# controller_rev3_1.net
KiCad netlist of a schematic drawn in EAGLE
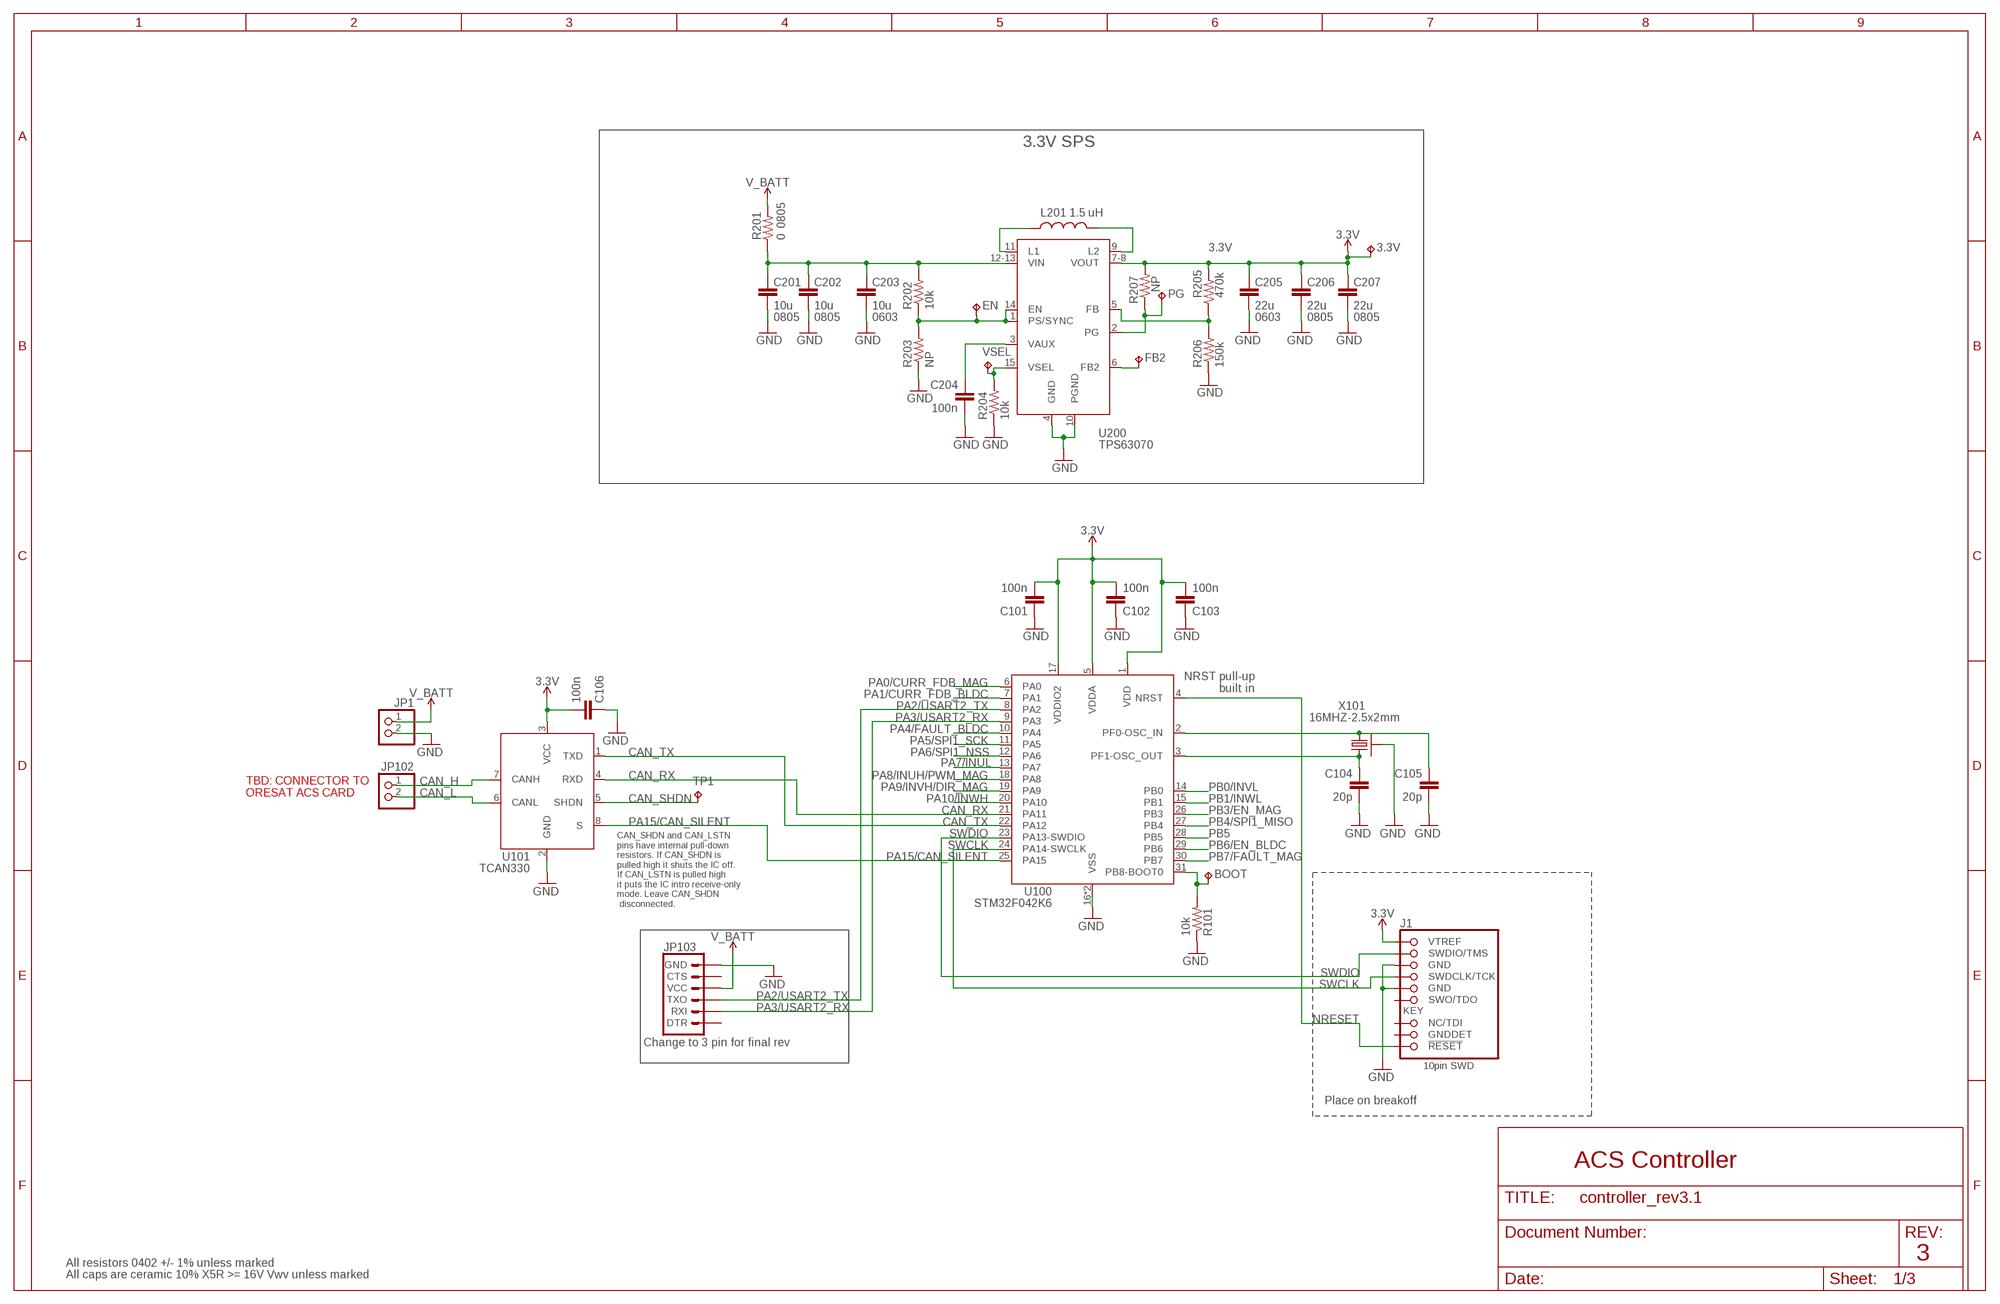
[diagram p0: schematic, sheet 1]
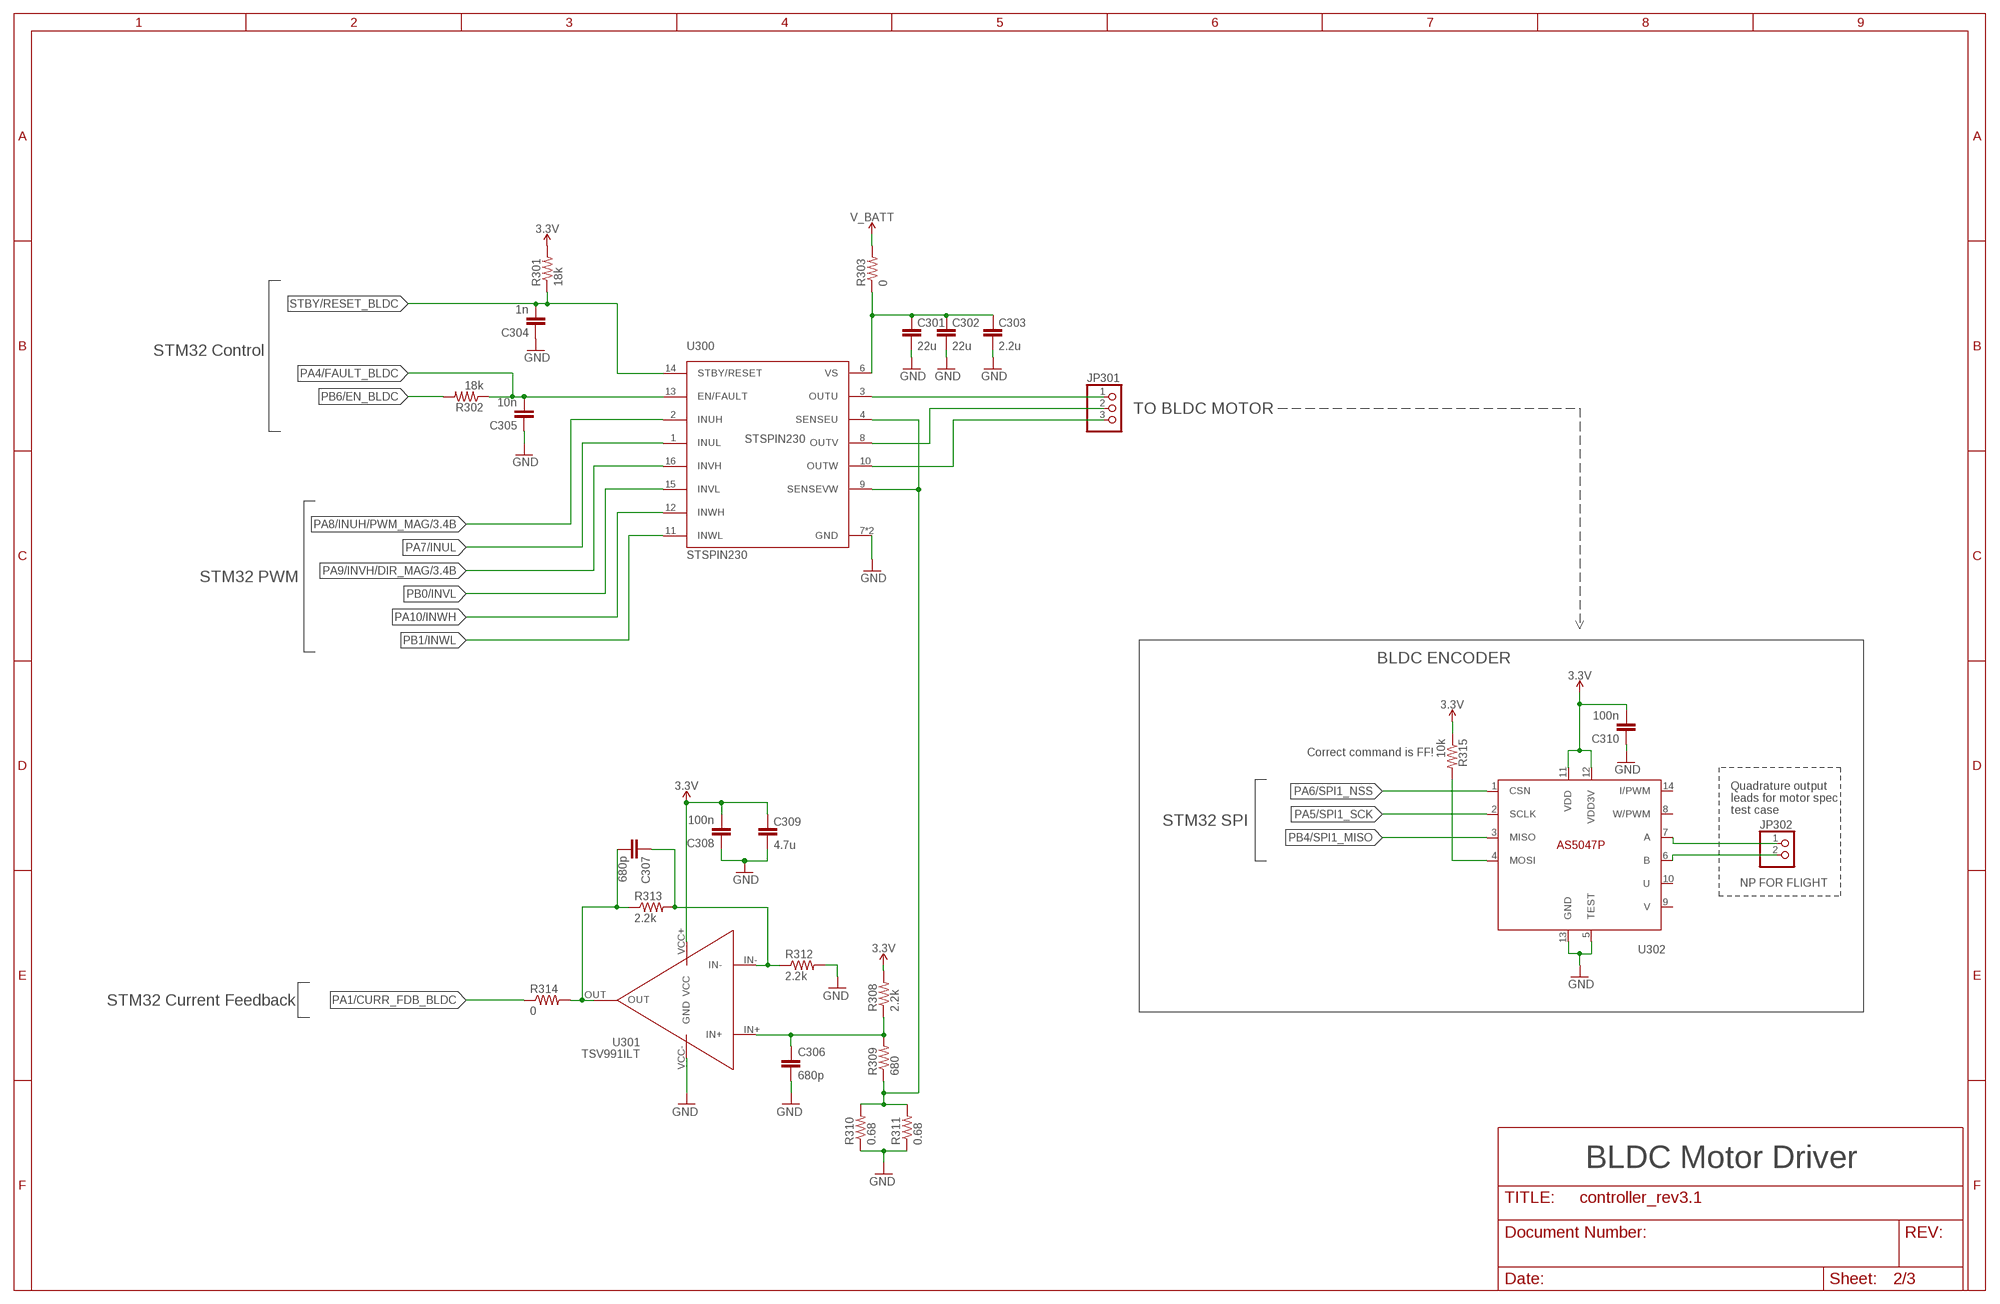
[diagram p1: schematic, sheet 2]
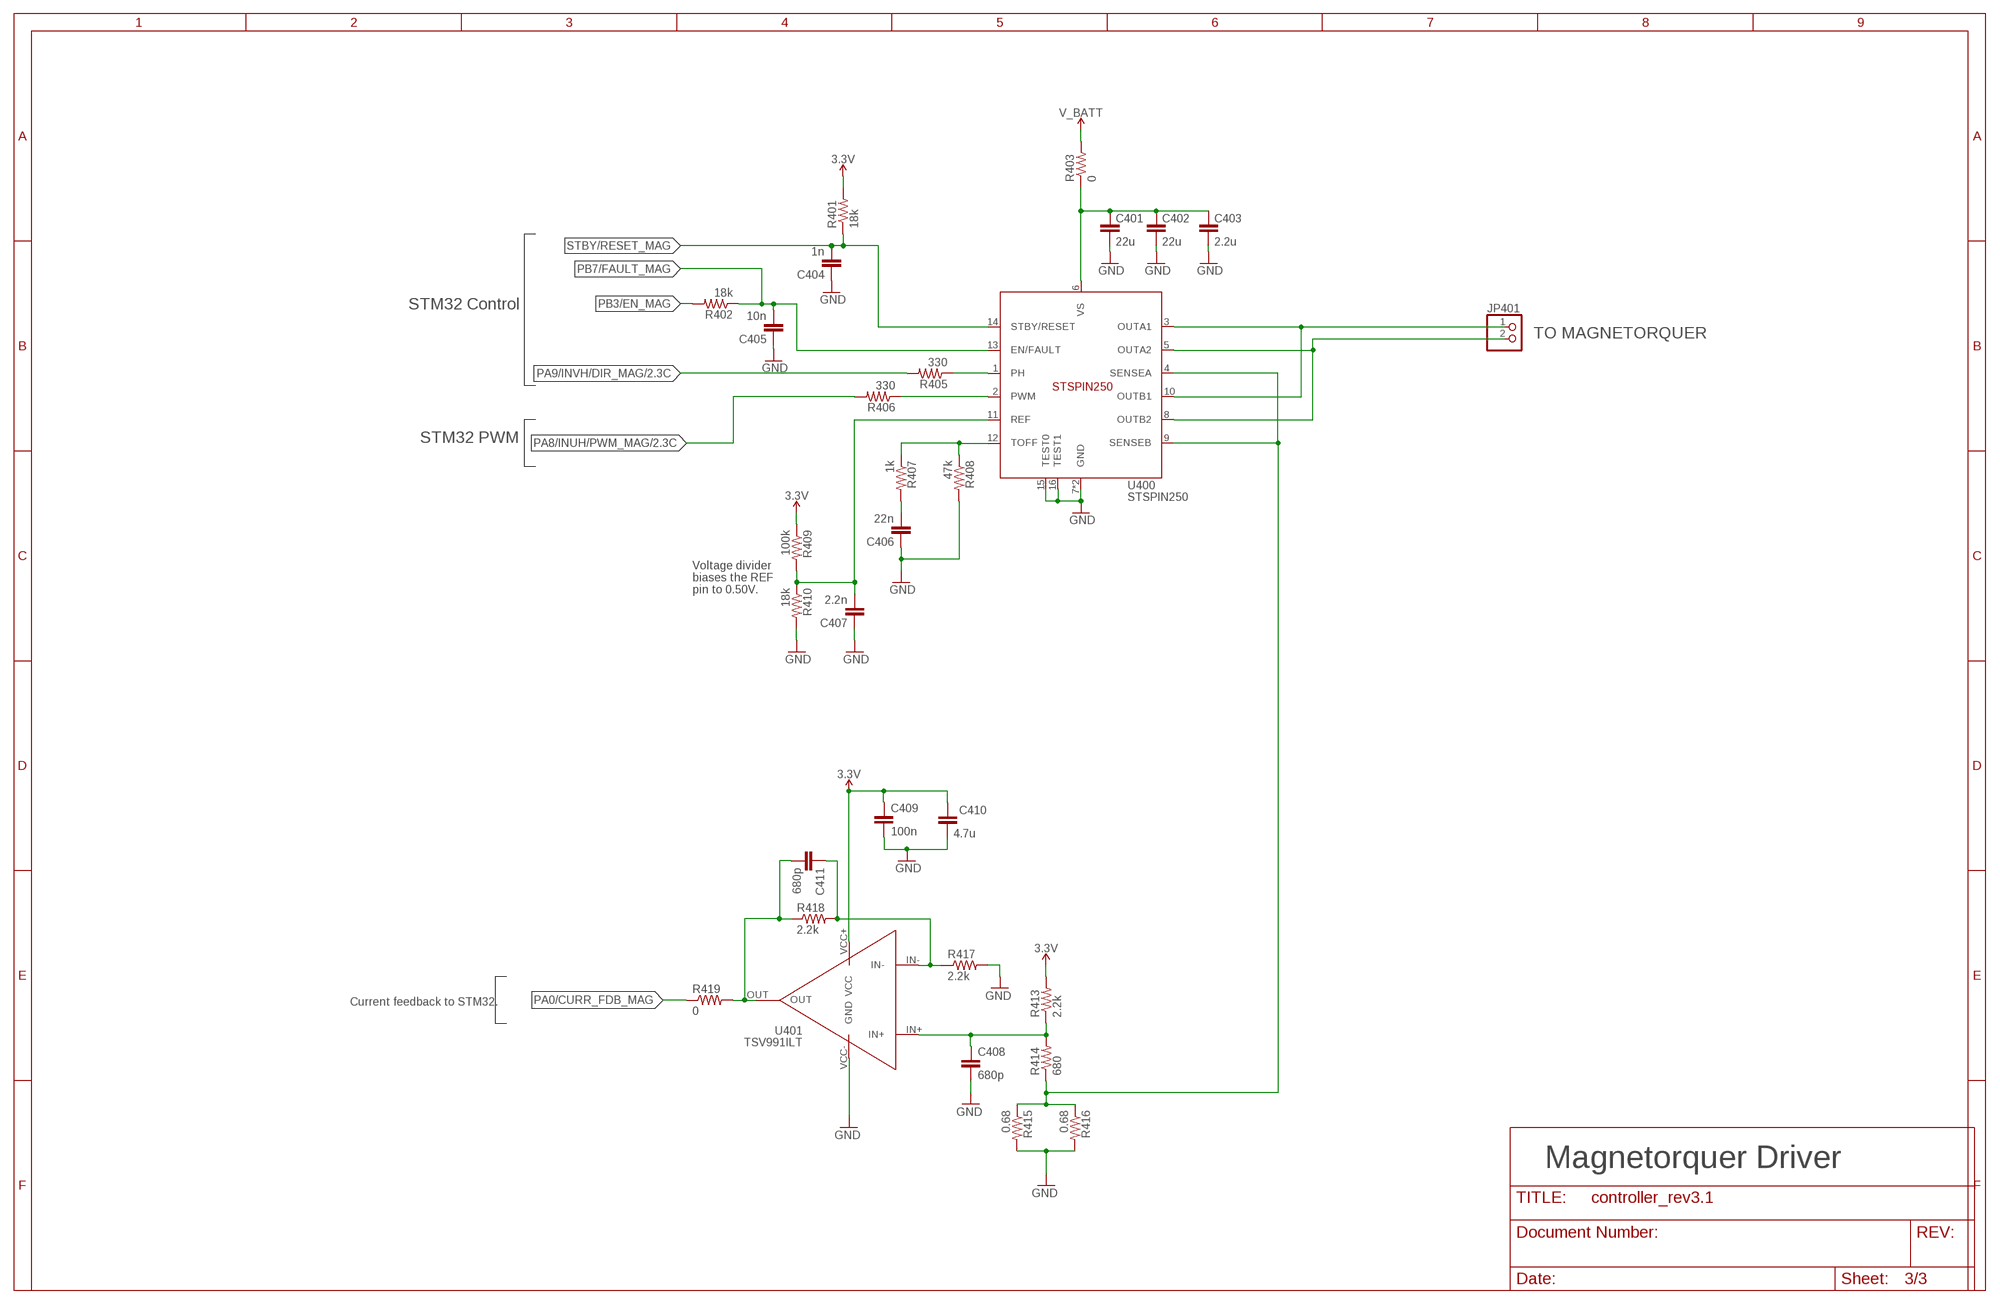
[diagram p2: schematic, sheet 3]

(export (version "E")
  (design (tool "Eeschema 10.0.6"))
  (components
    (comp (ref "3.3V")
      (value "TPTP15SQ")
      (footprint "eagle-import:TP15SQ")
      (libsource (lib "eagle-import") (part "TPTP15SQ"))
    )
    (comp (ref "BOOT")
      (value "TPTP15SQ")
      (footprint "eagle-import:TP15SQ")
      (libsource (lib "eagle-import") (part "TPTP15SQ"))
    )
    (comp (ref "C101")
      (value "100n")
      (footprint "eagle-import:.0402-B-NOSILK")
      (fields (field (name "MFR") "Samsung") (field (name "MPN") "CL05B104KO5NNNC"))
      (libsource (lib "eagle-import") (part "rcl_custom_C-EU0402-B-NOSILK"))
    )
    (comp (ref "C102")
      (value "100n")
      (footprint "eagle-import:.0402-B-NOSILK")
      (fields (field (name "MFR") "Samsung") (field (name "MPN") "CL05B104KO5NNNC"))
      (libsource (lib "eagle-import") (part "rcl_custom_C-EU0402-B-NOSILK"))
    )
    (comp (ref "C103")
      (value "100n")
      (footprint "eagle-import:.0402-B-NOSILK")
      (fields (field (name "MFR") "Samsung") (field (name "MPN") "CL05B104KO5NNNC"))
      (libsource (lib "eagle-import") (part "rcl_custom_C-EU0402-B-NOSILK"))
    )
    (comp (ref "C104")
      (value "20p")
      (footprint "eagle-import:.0402-B-NOSILK")
      (fields (field (name "MFR") "Samsung") (field (name "MPN") "CL05C200JB51PNC"))
      (libsource (lib "eagle-import") (part "rcl_custom_C-EU0402-B-NOSILK"))
    )
    (comp (ref "C105")
      (value "20p")
      (footprint "eagle-import:.0402-B-NOSILK")
      (fields (field (name "MFR") "Samsung") (field (name "MPN") "CL05C200JB51PNC"))
      (libsource (lib "eagle-import") (part "rcl_custom_C-EU0402-B-NOSILK"))
    )
    (comp (ref "C106")
      (value "100n")
      (footprint "eagle-import:.0402-B-NOSILK")
      (fields (field (name "MFR") "Samsung") (field (name "MPN") "CL05B104KO5NNNC"))
      (libsource (lib "eagle-import") (part "rcl_custom_C-EU0402-B-NOSILK"))
    )
    (comp (ref "C201")
      (value "10u")
      (footprint "eagle-import:.0805-B-NOSILK")
      (libsource (lib "eagle-import") (part "C-EU0805-B-NOSILK"))
    )
    (comp (ref "C202")
      (value "10u")
      (footprint "eagle-import:.0805-B-NOSILK")
      (libsource (lib "eagle-import") (part "C-EU0805-B-NOSILK"))
    )
    (comp (ref "C203")
      (value "10u")
      (footprint "eagle-import:.0603-B-NOSILK")
      (fields (field (name "MFR") "Samsung") (field (name "MPN") "CL05B104KO5NNNC"))
      (libsource (lib "eagle-import") (part "C-EU0603-B-NOSILK"))
    )
    (comp (ref "C204")
      (value "100n")
      (footprint "eagle-import:.0402-B-NOSILK")
      (fields (field (name "MFR") "Samsung") (field (name "MPN") "CL05B104KO5NNNC"))
      (libsource (lib "eagle-import") (part "rcl_custom_C-EU0402-B-NOSILK"))
    )
    (comp (ref "C205")
      (value "22u")
      (footprint "eagle-import:.0603-B-NOSILK")
      (fields (field (name "MFR") "Samsung") (field (name "MPN") "CL05B104KO5NNNC"))
      (libsource (lib "eagle-import") (part "C-EU0603-B-NOSILK"))
    )
    (comp (ref "C206")
      (value "22u")
      (footprint "eagle-import:.0805-B-NOSILK")
      (libsource (lib "eagle-import") (part "C-EU0805-B-NOSILK"))
    )
    (comp (ref "C207")
      (value "22u")
      (footprint "eagle-import:.0805-B-NOSILK")
      (libsource (lib "eagle-import") (part "C-EU0805-B-NOSILK"))
    )
    (comp (ref "EN")
      (value "TPTP15SQ")
      (footprint "eagle-import:TP15SQ")
      (libsource (lib "eagle-import") (part "TPTP15SQ"))
    )
    (comp (ref "FB2")
      (value "TPTP15SQ")
      (footprint "eagle-import:TP15SQ")
      (libsource (lib "eagle-import") (part "TPTP15SQ"))
    )
    (comp (ref "J1")
      (value "1.27MM-SWD-CONNECTOR")
      (footprint "eagle-import:1.27MM_2X5")
      (libsource (lib "eagle-import") (part "1.27MM-SWD-CONNECTOR"))
    )
    (comp (ref "JP1")
      (value "PINHD-1X2")
      (footprint "eagle-import:1X02")
      (libsource (lib "eagle-import") (part "PINHD-1X2"))
    )
    (comp (ref "JP102")
      (value "PINHD-1X2")
      (footprint "eagle-import:1X02")
      (libsource (lib "eagle-import") (part "PINHD-1X2"))
    )
    (comp (ref "JP103")
      (value "6_PIN_SERIAL_TARGETSILK")
      (footprint "eagle-import:6_PIN_SERIAL_TARGET_SIDE_W_SILK")
      (libsource (lib "eagle-import") (part "6_PIN_SERIAL_TARGETSILK"))
    )
    (comp (ref "L201")
      (value "1.5 uH")
      (footprint "eagle-import:L-COILCRAFT-XFL4020")
      (fields (field (name "MFR") "Coilcraft") (field (name "MPN") "XFL4020-152ME"))
      (libsource (lib "eagle-import") (part "L-COILCRAFT-XFL4020"))
    )
    (comp (ref "PG")
      (value "TPTP15SQ")
      (footprint "eagle-import:TP15SQ")
      (libsource (lib "eagle-import") (part "TPTP15SQ"))
    )
    (comp (ref "R101")
      (value "10k")
      (footprint "eagle-import:.0402-B-NOSILK")
      (fields (field (name "MFR") "Samsung") (field (name "MPN") "RC1005F6653CS"))
      (libsource (lib "eagle-import") (part "rcl_custom_R-US_0402-B-NOSILK"))
    )
    (comp (ref "R201")
      (value "0")
      (footprint "eagle-import:.0805-B-NOSILK")
      (fields (field (name "MFR") "Rohm") (field (name "MPN") "MCR10EZPJ000"))
      (libsource (lib "eagle-import") (part "rcl_custom_R-US_0805-B-NOSILK"))
    )
    (comp (ref "R202")
      (value "10k")
      (footprint "eagle-import:.0402-B-NOSILK")
      (fields (field (name "MFR") "Samsung") (field (name "MPN") "RC1005F6653CS"))
      (libsource (lib "eagle-import") (part "rcl_custom_R-US_0402-B-NOSILK"))
    )
    (comp (ref "R203")
      (value "NP")
      (footprint "eagle-import:.0402-B-NOSILK")
      (fields (field (name "MFR") "Samsung") (field (name "MPN") "RC1005F6653CS"))
      (libsource (lib "eagle-import") (part "rcl_custom_R-US_0402-B-NOSILK"))
    )
    (comp (ref "R204")
      (value "10k")
      (footprint "eagle-import:.0402-B-NOSILK")
      (fields (field (name "MFR") "Samsung") (field (name "MPN") "RC1005F6653CS"))
      (libsource (lib "eagle-import") (part "rcl_custom_R-US_0402-B-NOSILK"))
    )
    (comp (ref "R205")
      (value "470k")
      (footprint "eagle-import:.0402-B-NOSILK")
      (fields (field (name "MFR") "Samsung") (field (name "MPN") "RC1005F6653CS"))
      (libsource (lib "eagle-import") (part "rcl_custom_R-US_0402-B-NOSILK"))
    )
    (comp (ref "R206")
      (value "150k")
      (footprint "eagle-import:.0402-B-NOSILK")
      (fields (field (name "MFR") "Samsung") (field (name "MPN") "RC1005F6653CS"))
      (libsource (lib "eagle-import") (part "rcl_custom_R-US_0402-B-NOSILK"))
    )
    (comp (ref "R207")
      (value "NP")
      (footprint "eagle-import:.0402-B-NOSILK")
      (fields (field (name "MFR") "Samsung") (field (name "MPN") "RC1005F6653CS"))
      (libsource (lib "eagle-import") (part "rcl_custom_R-US_0402-B-NOSILK"))
    )
    (comp (ref "TP1")
      (value "TPTP06R")
      (footprint "eagle-import:TP06R")
      (libsource (lib "eagle-import") (part "TPTP06R"))
    )
    (comp (ref "U100")
      (value "STM32F042K6")
      (footprint "eagle-import:QFP32-7X7")
      (fields (field (name "MFR") "STMicroelectronics") (field (name "MPN") "STM32F042K6T7"))
      (libsource (lib "eagle-import") (part "STM32F042K6"))
    )
    (comp (ref "U101")
      (value "TCAN330")
      (footprint "eagle-import:SOT23-8_TI-DCN")
      (fields (field (name "MFR") "Texas Instruments") (field (name "MPN") "TCAN330GDCNT"))
      (libsource (lib "eagle-import") (part "TCAN330"))
    )
    (comp (ref "U200")
      (value "TPS63070")
      (footprint "eagle-import:TPS63070X")
      (libsource (lib "eagle-import") (part "TPS63070X"))
    )
    (comp (ref "VSEL")
      (value "TPTP15SQ")
      (footprint "eagle-import:TP15SQ")
      (libsource (lib "eagle-import") (part "TPTP15SQ"))
    )
    (comp (ref "X101")
      (value "16MHZ-2.5x2mm")
      (footprint "eagle-import:CRYSTAL_2.5X2")
      (fields (field (name "MFR") "ECS Inc.") (field (name "MPN") "ECS-160-10-36Q-ES-TR"))
      (libsource (lib "eagle-import") (part "CRYSTAL-WITH-GND"))
    )
    (comp (ref "C401")
      (value "22u")
      (footprint "eagle-import:.0603-B-NOSILK")
      (fields (field (name "MFR") "Samsung") (field (name "MPN") "CL05B104KO5NNNC"))
      (libsource (lib "eagle-import") (part "C-EU0603-B-NOSILK"))
    )
    (comp (ref "C402")
      (value "22u")
      (footprint "eagle-import:.0603-B-NOSILK")
      (fields (field (name "MFR") "Samsung") (field (name "MPN") "CL05B104KO5NNNC"))
      (libsource (lib "eagle-import") (part "C-EU0603-B-NOSILK"))
    )
    (comp (ref "C403")
      (value "2.2u")
      (footprint "eagle-import:.0603-B-NOSILK")
      (fields (field (name "MFR") "Samsung") (field (name "MPN") "CL05B104KO5NNNC"))
      (libsource (lib "eagle-import") (part "C-EU0603-B-NOSILK"))
    )
    (comp (ref "C404")
      (value "1n")
      (footprint "eagle-import:.0402-B-NOSILK")
      (fields (field (name "MFR") "Samsung") (field (name "MPN") "CL05B104KO5NNNC"))
      (libsource (lib "eagle-import") (part "rcl_custom_C-EU0402-B-NOSILK"))
    )
    (comp (ref "C405")
      (value "10n")
      (footprint "eagle-import:.0402-B-NOSILK")
      (fields (field (name "MFR") "Samsung") (field (name "MPN") "CL05B104KO5NNNC"))
      (libsource (lib "eagle-import") (part "rcl_custom_C-EU0402-B-NOSILK"))
    )
    (comp (ref "C406")
      (value "22n")
      (footprint "eagle-import:.0402-B-NOSILK")
      (fields (field (name "MFR") "Samsung") (field (name "MPN") "CL05B104KO5NNNC"))
      (libsource (lib "eagle-import") (part "rcl_custom_C-EU0402-B-NOSILK"))
    )
    (comp (ref "C407")
      (value "2.2n")
      (footprint "eagle-import:.0402-B-NOSILK")
      (fields (field (name "MFR") "Samsung") (field (name "MPN") "CL05B104KO5NNNC"))
      (libsource (lib "eagle-import") (part "rcl_custom_C-EU0402-B-NOSILK"))
    )
    (comp (ref "C408")
      (value "680p")
      (footprint "eagle-import:.0402-B-NOSILK")
      (fields (field (name "MFR") "Samsung") (field (name "MPN") "CL05B104KO5NNNC"))
      (libsource (lib "eagle-import") (part "rcl_custom_C-EU0402-B-NOSILK"))
    )
    (comp (ref "C409")
      (value "100n")
      (footprint "eagle-import:.0402-B-NOSILK")
      (fields (field (name "MFR") "Samsung") (field (name "MPN") "CL05B104KO5NNNC"))
      (libsource (lib "eagle-import") (part "rcl_custom_C-EU0402-B-NOSILK"))
    )
    (comp (ref "C410")
      (value "4.7u")
      (footprint "eagle-import:.0603-B-NOSILK")
      (fields (field (name "MFR") "Samsung") (field (name "MPN") "CL05B104KO5NNNC"))
      (libsource (lib "eagle-import") (part "C-EU0603-B-NOSILK"))
    )
    (comp (ref "C411")
      (value "680p")
      (footprint "eagle-import:.0402-B-NOSILK")
      (fields (field (name "MFR") "Samsung") (field (name "MPN") "CL05B104KO5NNNC"))
      (libsource (lib "eagle-import") (part "rcl_custom_C-EU0402-B-NOSILK"))
    )
    (comp (ref "JP401")
      (value "PINHD-1X2")
      (footprint "eagle-import:1X02")
      (libsource (lib "eagle-import") (part "PINHD-1X2"))
    )
    (comp (ref "R401")
      (value "18k")
      (footprint "eagle-import:.0402-B-NOSILK")
      (fields (field (name "MFR") "Samsung") (field (name "MPN") "RC1005F6653CS"))
      (libsource (lib "eagle-import") (part "rcl_custom_R-US_0402-B-NOSILK"))
    )
    (comp (ref "R402")
      (value "18k")
      (footprint "eagle-import:.0402-B-NOSILK")
      (fields (field (name "MFR") "Samsung") (field (name "MPN") "RC1005F6653CS"))
      (libsource (lib "eagle-import") (part "rcl_custom_R-US_0402-B-NOSILK"))
    )
    (comp (ref "R403")
      (value "0")
      (footprint "eagle-import:.0805-B-NOSILK")
      (libsource (lib "eagle-import") (part "R-US_0805-B-NOSILK"))
    )
    (comp (ref "R405")
      (value "330")
      (footprint "eagle-import:.0402-B-NOSILK")
      (fields (field (name "MFR") "Samsung") (field (name "MPN") "RC1005F6653CS"))
      (libsource (lib "eagle-import") (part "rcl_custom_R-US_0402-B-NOSILK"))
    )
    (comp (ref "R406")
      (value "330")
      (footprint "eagle-import:.0402-B-NOSILK")
      (fields (field (name "MFR") "Samsung") (field (name "MPN") "RC1005F6653CS"))
      (libsource (lib "eagle-import") (part "rcl_custom_R-US_0402-B-NOSILK"))
    )
    (comp (ref "R407")
      (value "1k")
      (footprint "eagle-import:.0402-B-NOSILK")
      (fields (field (name "MFR") "Samsung") (field (name "MPN") "RC1005F6653CS"))
      (libsource (lib "eagle-import") (part "rcl_custom_R-US_0402-B-NOSILK"))
    )
    (comp (ref "R408")
      (value "47k")
      (footprint "eagle-import:.0402-B-NOSILK")
      (fields (field (name "MFR") "Samsung") (field (name "MPN") "RC1005F6653CS"))
      (libsource (lib "eagle-import") (part "rcl_custom_R-US_0402-B-NOSILK"))
    )
    (comp (ref "R409")
      (value "100k")
      (footprint "eagle-import:.0402-B-NOSILK")
      (fields (field (name "MFR") "Samsung") (field (name "MPN") "RC1005F6653CS"))
      (libsource (lib "eagle-import") (part "rcl_custom_R-US_0402-B-NOSILK"))
    )
    (comp (ref "R410")
      (value "18k")
      (footprint "eagle-import:.0402-B-NOSILK")
      (fields (field (name "MFR") "Samsung") (field (name "MPN") "RC1005F6653CS"))
      (libsource (lib "eagle-import") (part "rcl_custom_R-US_0402-B-NOSILK"))
    )
    (comp (ref "R413")
      (value "2.2k")
      (footprint "eagle-import:.0402-B-NOSILK")
      (fields (field (name "MFR") "Samsung") (field (name "MPN") "RC1005F6653CS"))
      (libsource (lib "eagle-import") (part "rcl_custom_R-US_0402-B-NOSILK"))
    )
    (comp (ref "R414")
      (value "680")
      (footprint "eagle-import:.0402-B-NOSILK")
      (fields (field (name "MFR") "Samsung") (field (name "MPN") "RC1005F6653CS"))
      (libsource (lib "eagle-import") (part "rcl_custom_R-US_0402-B-NOSILK"))
    )
    (comp (ref "R415")
      (value "0.68")
      (footprint "eagle-import:.0805-B-NOSILK")
      (libsource (lib "eagle-import") (part "R-US_0805-B-NOSILK"))
    )
    (comp (ref "R416")
      (value "0.68")
      (footprint "eagle-import:.0805-B-NOSILK")
      (libsource (lib "eagle-import") (part "R-US_0805-B-NOSILK"))
    )
    (comp (ref "R417")
      (value "2.2k")
      (footprint "eagle-import:.0402-B-NOSILK")
      (fields (field (name "MFR") "Samsung") (field (name "MPN") "RC1005F6653CS"))
      (libsource (lib "eagle-import") (part "rcl_custom_R-US_0402-B-NOSILK"))
    )
    (comp (ref "R418")
      (value "2.2k")
      (footprint "eagle-import:.0402-B-NOSILK")
      (fields (field (name "MFR") "Samsung") (field (name "MPN") "RC1005F6653CS"))
      (libsource (lib "eagle-import") (part "rcl_custom_R-US_0402-B-NOSILK"))
    )
    (comp (ref "R419")
      (value "0")
      (footprint "eagle-import:.0402-B-NOSILK")
      (fields (field (name "MFR") "Samsung") (field (name "MPN") "RC1005F6653CS"))
      (libsource (lib "eagle-import") (part "rcl_custom_R-US_0402-B-NOSILK"))
    )
    (comp (ref "U400")
      (value "STSPIN250")
      (footprint "eagle-import:VFQPN")
      (libsource (lib "eagle-import") (part "STSPIN250"))
    )
    (comp (ref "U401")
      (value "TSV991ILT")
      (footprint "eagle-import:SOT23-5")
      (libsource (lib "eagle-import") (part "TSV991ILT"))
    )
    (comp (ref "C301")
      (value "22u")
      (footprint "eagle-import:.0603-B-NOSILK")
      (fields (field (name "MFR") "Samsung") (field (name "MPN") "CL05B104KO5NNNC"))
      (libsource (lib "eagle-import") (part "C-EU0603-B-NOSILK"))
    )
    (comp (ref "C302")
      (value "22u")
      (footprint "eagle-import:.0603-B-NOSILK")
      (fields (field (name "MFR") "Samsung") (field (name "MPN") "CL05B104KO5NNNC"))
      (libsource (lib "eagle-import") (part "C-EU0603-B-NOSILK"))
    )
    (comp (ref "C303")
      (value "2.2u")
      (footprint "eagle-import:.0603-B-NOSILK")
      (fields (field (name "MFR") "Samsung") (field (name "MPN") "CL05B104KO5NNNC"))
      (libsource (lib "eagle-import") (part "C-EU0603-B-NOSILK"))
    )
    (comp (ref "C304")
      (value "1n")
      (footprint "eagle-import:.0402-B-NOSILK")
      (fields (field (name "MFR") "Samsung") (field (name "MPN") "CL05B104KO5NNNC"))
      (libsource (lib "eagle-import") (part "rcl_custom_C-EU0402-B-NOSILK"))
    )
    (comp (ref "C305")
      (value "10n")
      (footprint "eagle-import:.0402-B-NOSILK")
      (fields (field (name "MFR") "Samsung") (field (name "MPN") "CL05B104KO5NNNC"))
      (libsource (lib "eagle-import") (part "rcl_custom_C-EU0402-B-NOSILK"))
    )
    (comp (ref "C306")
      (value "680p")
      (footprint "eagle-import:.0402-B-NOSILK")
      (fields (field (name "MFR") "Samsung") (field (name "MPN") "CL05B104KO5NNNC"))
      (libsource (lib "eagle-import") (part "rcl_custom_C-EU0402-B-NOSILK"))
    )
    (comp (ref "C307")
      (value "680p")
      (footprint "eagle-import:.0402-B-NOSILK")
      (fields (field (name "MFR") "Samsung") (field (name "MPN") "CL05B104KO5NNNC"))
      (libsource (lib "eagle-import") (part "rcl_custom_C-EU0402-B-NOSILK"))
    )
    (comp (ref "C308")
      (value "100n")
      (footprint "eagle-import:.0402-B-NOSILK")
      (fields (field (name "MFR") "Samsung") (field (name "MPN") "CL05B104KO5NNNC"))
      (libsource (lib "eagle-import") (part "rcl_custom_C-EU0402-B-NOSILK"))
    )
    (comp (ref "C309")
      (value "4.7u")
      (footprint "eagle-import:.0603-B-NOSILK")
      (fields (field (name "MFR") "Samsung") (field (name "MPN") "CL05B104KO5NNNC"))
      (libsource (lib "eagle-import") (part "C-EU0603-B-NOSILK"))
    )
    (comp (ref "C310")
      (value "100n")
      (footprint "eagle-import:.0402-B-NOSILK")
      (fields (field (name "MFR") "Samsung") (field (name "MPN") "CL05B104KO5NNNC"))
      (libsource (lib "eagle-import") (part "rcl_custom_C-EU0402-B-NOSILK"))
    )
    (comp (ref "JP301")
      (value "PINHD-1X03_2.00")
      (footprint "eagle-import:1X03M")
      (libsource (lib "eagle-import") (part "PINHD-1X03_2.00"))
    )
    (comp (ref "JP302")
      (value "PINHD-1X2")
      (footprint "eagle-import:1X02")
      (libsource (lib "eagle-import") (part "PINHD-1X2"))
    )
    (comp (ref "R301")
      (value "18k")
      (footprint "eagle-import:.0402-B-NOSILK")
      (fields (field (name "MFR") "Samsung") (field (name "MPN") "RC1005F6653CS"))
      (libsource (lib "eagle-import") (part "rcl_custom_R-US_0402-B-NOSILK"))
    )
    (comp (ref "R302")
      (value "18k")
      (footprint "eagle-import:.0402-B-NOSILK")
      (fields (field (name "MFR") "Samsung") (field (name "MPN") "RC1005F6653CS"))
      (libsource (lib "eagle-import") (part "rcl_custom_R-US_0402-B-NOSILK"))
    )
    (comp (ref "R303")
      (value "0")
      (footprint "eagle-import:.0805-B-NOSILK")
      (libsource (lib "eagle-import") (part "R-US_0805-B-NOSILK"))
    )
    (comp (ref "R308")
      (value "2.2k")
      (footprint "eagle-import:.0402-B-NOSILK")
      (fields (field (name "MFR") "Samsung") (field (name "MPN") "RC1005F6653CS"))
      (libsource (lib "eagle-import") (part "rcl_custom_R-US_0402-B-NOSILK"))
    )
    (comp (ref "R309")
      (value "680")
      (footprint "eagle-import:.0402-B-NOSILK")
      (fields (field (name "MFR") "Samsung") (field (name "MPN") "RC1005F6653CS"))
      (libsource (lib "eagle-import") (part "rcl_custom_R-US_0402-B-NOSILK"))
    )
    (comp (ref "R310")
      (value "0.68")
      (footprint "eagle-import:.0805-B-NOSILK")
      (libsource (lib "eagle-import") (part "R-US_0805-B-NOSILK"))
    )
    (comp (ref "R311")
      (value "0.68")
      (footprint "eagle-import:.0805-B-NOSILK")
      (libsource (lib "eagle-import") (part "R-US_0805-B-NOSILK"))
    )
    (comp (ref "R312")
      (value "2.2k")
      (footprint "eagle-import:.0402-B-NOSILK")
      (fields (field (name "MFR") "Samsung") (field (name "MPN") "RC1005F6653CS"))
      (libsource (lib "eagle-import") (part "rcl_custom_R-US_0402-B-NOSILK"))
    )
    (comp (ref "R313")
      (value "2.2k")
      (footprint "eagle-import:.0402-B-NOSILK")
      (fields (field (name "MFR") "Samsung") (field (name "MPN") "RC1005F6653CS"))
      (libsource (lib "eagle-import") (part "rcl_custom_R-US_0402-B-NOSILK"))
    )
    (comp (ref "R314")
      (value "0")
      (footprint "eagle-import:.0402-B-NOSILK")
      (fields (field (name "MFR") "Samsung") (field (name "MPN") "RC1005F6653CS"))
      (libsource (lib "eagle-import") (part "rcl_custom_R-US_0402-B-NOSILK"))
    )
    (comp (ref "R315")
      (value "10k")
      (footprint "eagle-import:.0402-B-NOSILK")
      (fields (field (name "MFR") "Samsung") (field (name "MPN") "RC1005F6653CS"))
      (libsource (lib "eagle-import") (part "rcl_custom_R-US_0402-B-NOSILK"))
    )
    (comp (ref "U300")
      (value "STSPIN230")
      (footprint "eagle-import:VFQFPN")
      (libsource (lib "eagle-import") (part "STSPIN230"))
    )
    (comp (ref "U301")
      (value "TSV991ILT")
      (footprint "eagle-import:SOT23-5")
      (libsource (lib "eagle-import") (part "TSV991ILT"))
    )
    (comp (ref "U302")
      (value "AS5047P")
      (footprint "eagle-import:TSSOP14")
      (libsource (lib "eagle-import") (part "AS5047P"))
    )
  )
  (nets
    (net (code "1") (name "3.3V") (class "Default")
      (node (ref "3.3V") (pin "TP") (pinfunction "TP_TP") (pintype "input"))
      (node (ref "C101") (pin "2") (pinfunction "2_2") (pintype "passive"))
      (node (ref "C102") (pin "2") (pinfunction "2_2") (pintype "passive"))
      (node (ref "C103") (pin "2") (pinfunction "2_2") (pintype "passive"))
      (node (ref "C106") (pin "2") (pinfunction "2_2") (pintype "passive"))
      (node (ref "C205") (pin "1") (pinfunction "1_1") (pintype "passive"))
      (node (ref "C206") (pin "1") (pinfunction "1_1") (pintype "passive"))
      (node (ref "C207") (pin "1") (pinfunction "1_1") (pintype "passive"))
      (node (ref "C308") (pin "2") (pinfunction "2_2") (pintype "passive"))
      (node (ref "C309") (pin "1") (pinfunction "1_1") (pintype "passive"))
      (node (ref "C310") (pin "2") (pinfunction "2_2") (pintype "passive"))
      (node (ref "C409") (pin "1") (pinfunction "1_1") (pintype "passive"))
      (node (ref "C410") (pin "1") (pinfunction "1_1") (pintype "passive"))
      (node (ref "J1") (pin "VTREF") (pinfunction "VTREF_VTREF") (pintype "passive"))
      (node (ref "R205") (pin "2") (pinfunction "2_2") (pintype "passive"))
      (node (ref "R207") (pin "2") (pinfunction "2_2") (pintype "passive"))
      (node (ref "R301") (pin "2") (pinfunction "2_2") (pintype "passive"))
      (node (ref "R308") (pin "2") (pinfunction "2_2") (pintype "passive"))
      (node (ref "R315") (pin "1") (pinfunction "1_1") (pintype "passive"))
      (node (ref "R401") (pin "2") (pinfunction "2_2") (pintype "passive"))
      (node (ref "R409") (pin "1") (pinfunction "1_1") (pintype "passive"))
      (node (ref "R413") (pin "2") (pinfunction "2_2") (pintype "passive"))
      (node (ref "U100") (pin "1") (pinfunction "VDD_1") (pintype "power_in"))
      (node (ref "U100") (pin "17") (pinfunction "VDDIO2_17") (pintype "power_in"))
      (node (ref "U100") (pin "5") (pinfunction "VDDA_5") (pintype "power_in"))
      (node (ref "U101") (pin "3") (pinfunction "VCC_3") (pintype "power_in"))
      (node (ref "U200") (pin "7-8") (pinfunction "VOUT_7-8") (pintype "power_in"))
      (node (ref "U301") (pin "VCC+") (pinfunction "VCC_VCC+") (pintype "bidirectional"))
      (node (ref "U302") (pin "11") (pinfunction "VDD_11") (pintype "power_in"))
      (node (ref "U302") (pin "12") (pinfunction "VDD3V_12") (pintype "power_in"))
      (node (ref "U401") (pin "VCC+") (pinfunction "VCC_VCC+") (pintype "bidirectional"))
    )
    (net (code "2") (name "CAN_H") (class "Default")
      (node (ref "JP102") (pin "1") (pinfunction "1_1") (pintype "passive"))
      (node (ref "U101") (pin "7") (pinfunction "CANH_7") (pintype "bidirectional"))
    )
    (net (code "3") (name "CAN_L") (class "Default")
      (node (ref "JP102") (pin "2") (pinfunction "2_2") (pintype "passive"))
      (node (ref "U101") (pin "6") (pinfunction "CANL_6") (pintype "bidirectional"))
    )
    (net (code "4") (name "CAN_RX") (class "Default")
      (node (ref "U100") (pin "21") (pinfunction "PA11_21") (pintype "bidirectional"))
      (node (ref "U101") (pin "4") (pinfunction "RXD_4") (pintype "output"))
    )
    (net (code "5") (name "CAN_SHDN") (class "Default")
      (node (ref "TP1") (pin "TP") (pinfunction "TP_TP") (pintype "input"))
      (node (ref "U101") (pin "5") (pinfunction "SHDN_5") (pintype "input"))
    )
    (net (code "6") (name "CAN_TX") (class "Default")
      (node (ref "U100") (pin "22") (pinfunction "PA12_22") (pintype "bidirectional"))
      (node (ref "U101") (pin "1") (pinfunction "TXD_1") (pintype "input"))
    )
    (net (code "7") (name "GND") (class "Default")
      (node (ref "C101") (pin "1") (pinfunction "1_1") (pintype "passive"))
      (node (ref "C102") (pin "1") (pinfunction "1_1") (pintype "passive"))
      (node (ref "C103") (pin "1") (pinfunction "1_1") (pintype "passive"))
      (node (ref "C104") (pin "2") (pinfunction "2_2") (pintype "passive"))
      (node (ref "C105") (pin "2") (pinfunction "2_2") (pintype "passive"))
      (node (ref "C106") (pin "1") (pinfunction "1_1") (pintype "passive"))
      (node (ref "C201") (pin "2") (pinfunction "2_2") (pintype "passive"))
      (node (ref "C202") (pin "2") (pinfunction "2_2") (pintype "passive"))
      (node (ref "C203") (pin "2") (pinfunction "2_2") (pintype "passive"))
      (node (ref "C204") (pin "2") (pinfunction "2_2") (pintype "passive"))
      (node (ref "C205") (pin "2") (pinfunction "2_2") (pintype "passive"))
      (node (ref "C206") (pin "2") (pinfunction "2_2") (pintype "passive"))
      (node (ref "C207") (pin "2") (pinfunction "2_2") (pintype "passive"))
      (node (ref "C301") (pin "2") (pinfunction "2_2") (pintype "passive"))
      (node (ref "C302") (pin "2") (pinfunction "2_2") (pintype "passive"))
      (node (ref "C303") (pin "2") (pinfunction "2_2") (pintype "passive"))
      (node (ref "C304") (pin "1") (pinfunction "1_1") (pintype "passive"))
      (node (ref "C305") (pin "1") (pinfunction "1_1") (pintype "passive"))
      (node (ref "C306") (pin "2") (pinfunction "2_2") (pintype "passive"))
      (node (ref "C308") (pin "1") (pinfunction "1_1") (pintype "passive"))
      (node (ref "C309") (pin "2") (pinfunction "2_2") (pintype "passive"))
      (node (ref "C310") (pin "1") (pinfunction "1_1") (pintype "passive"))
      (node (ref "C401") (pin "2") (pinfunction "2_2") (pintype "passive"))
      (node (ref "C402") (pin "2") (pinfunction "2_2") (pintype "passive"))
      (node (ref "C403") (pin "2") (pinfunction "2_2") (pintype "passive"))
      (node (ref "C404") (pin "1") (pinfunction "1_1") (pintype "passive"))
      (node (ref "C405") (pin "1") (pinfunction "1_1") (pintype "passive"))
      (node (ref "C406") (pin "1") (pinfunction "1_1") (pintype "passive"))
      (node (ref "C407") (pin "1") (pinfunction "1_1") (pintype "passive"))
      (node (ref "C408") (pin "2") (pinfunction "2_2") (pintype "passive"))
      (node (ref "C409") (pin "2") (pinfunction "2_2") (pintype "passive"))
      (node (ref "C410") (pin "2") (pinfunction "2_2") (pintype "passive"))
      (node (ref "J1") (pin "GND") (pinfunction "GND_GND") (pintype "passive"))
      (node (ref "J1") (pin "GND@2") (pinfunction "GND_GND@2") (pintype "passive"))
      (node (ref "JP1") (pin "2") (pinfunction "2_2") (pintype "passive"))
      (node (ref "JP103") (pin "P$6") (pinfunction "GND_P$6") (pintype "passive"))
      (node (ref "R101") (pin "1") (pinfunction "1_1") (pintype "passive"))
      (node (ref "R203") (pin "1") (pinfunction "1_1") (pintype "passive"))
      (node (ref "R204") (pin "1") (pinfunction "1_1") (pintype "passive"))
      (node (ref "R206") (pin "1") (pinfunction "1_1") (pintype "passive"))
      (node (ref "R310") (pin "1") (pinfunction "1_1") (pintype "passive"))
      (node (ref "R311") (pin "1") (pinfunction "1_1") (pintype "passive"))
      (node (ref "R312") (pin "2") (pinfunction "2_2") (pintype "passive"))
      (node (ref "R408") (pin "2") (pinfunction "2_2") (pintype "passive"))
      (node (ref "R410") (pin "2") (pinfunction "2_2") (pintype "passive"))
      (node (ref "R415") (pin "2") (pinfunction "2_2") (pintype "passive"))
      (node (ref "R416") (pin "2") (pinfunction "2_2") (pintype "passive"))
      (node (ref "R417") (pin "2") (pinfunction "2_2") (pintype "passive"))
      (node (ref "U100") (pin "16") (pinfunction "VSS_16") (pintype "power_in"))
      (node (ref "U100") (pin "32") (pinfunction "VSS_32") (pintype "power_in"))
      (node (ref "U101") (pin "2") (pinfunction "GND_2") (pintype "power_in"))
      (node (ref "U200") (pin "10") (pinfunction "PGND_10") (pintype "power_in"))
      (node (ref "U200") (pin "4") (pinfunction "GND_4") (pintype "power_in"))
      (node (ref "U300") (pin "7") (pinfunction "GND_7") (pintype "power_in"))
      (node (ref "U300") (pin "EPAD") (pinfunction "GND_EPAD") (pintype "power_in"))
      (node (ref "U301") (pin "VCC-") (pinfunction "GND_VCC-") (pintype "bidirectional"))
      (node (ref "U302") (pin "13") (pinfunction "GND_13") (pintype "power_in"))
      (node (ref "U302") (pin "5") (pinfunction "TEST_5") (pintype "power_in"))
      (node (ref "U400") (pin "15") (pinfunction "TEST0_15") (pintype "bidirectional"))
      (node (ref "U400") (pin "16") (pinfunction "TEST1_16") (pintype "bidirectional"))
      (node (ref "U400") (pin "7") (pinfunction "GND_7") (pintype "power_in"))
      (node (ref "U400") (pin "EPAD") (pinfunction "GND_EPAD") (pintype "power_in"))
      (node (ref "U401") (pin "VCC-") (pinfunction "GND_VCC-") (pintype "bidirectional"))
      (node (ref "X101") (pin "2") (pinfunction "SHIELD_2") (pintype "power_in"))
      (node (ref "X101") (pin "4") (pinfunction "SHIELD_4") (pintype "power_in"))
    )
    (net (code "8") (name "NRESET") (class "Default")
      (node (ref "J1") (pin "!RESET") (pinfunction "~{RESET}_!RESET") (pintype "passive"))
      (node (ref "U100") (pin "4") (pinfunction "NRST_4") (pintype "bidirectional"))
    )
    (net (code "9") (name "Net-(C306-Pad1)") (class "Default")
      (node (ref "C306") (pin "1") (pinfunction "1_1") (pintype "passive"))
      (node (ref "R308") (pin "1") (pinfunction "1_1") (pintype "passive"))
      (node (ref "R309") (pin "2") (pinfunction "2_2") (pintype "passive"))
      (node (ref "U301") (pin "IN+") (pinfunction "IN+_IN+") (pintype "bidirectional"))
    )
    (net (code "10") (name "Net-(C307-Pad1)") (class "Default")
      (node (ref "C307") (pin "1") (pinfunction "1_1") (pintype "passive"))
      (node (ref "R312") (pin "1") (pinfunction "1_1") (pintype "passive"))
      (node (ref "R313") (pin "2") (pinfunction "2_2") (pintype "passive"))
      (node (ref "U301") (pin "IN-") (pinfunction "IN-_IN-") (pintype "bidirectional"))
    )
    (net (code "11") (name "Net-(C307-Pad2)") (class "Default")
      (node (ref "C307") (pin "2") (pinfunction "2_2") (pintype "passive"))
      (node (ref "R313") (pin "1") (pinfunction "1_1") (pintype "passive"))
      (node (ref "R314") (pin "2") (pinfunction "2_2") (pintype "passive"))
      (node (ref "U301") (pin "OUT") (pinfunction "OUT_OUT") (pintype "bidirectional"))
    )
    (net (code "12") (name "Net-(C406-Pad2)") (class "Default")
      (node (ref "C406") (pin "2") (pinfunction "2_2") (pintype "passive"))
      (node (ref "R407") (pin "2") (pinfunction "2_2") (pintype "passive"))
    )
    (net (code "13") (name "Net-(C408-Pad1)") (class "Default")
      (node (ref "C408") (pin "1") (pinfunction "1_1") (pintype "passive"))
      (node (ref "R413") (pin "1") (pinfunction "1_1") (pintype "passive"))
      (node (ref "R414") (pin "2") (pinfunction "2_2") (pintype "passive"))
      (node (ref "U401") (pin "IN+") (pinfunction "IN+_IN+") (pintype "bidirectional"))
    )
    (net (code "14") (name "Net-(C411-Pad1)") (class "Default")
      (node (ref "C411") (pin "1") (pinfunction "1_1") (pintype "passive"))
      (node (ref "R417") (pin "1") (pinfunction "1_1") (pintype "passive"))
      (node (ref "R418") (pin "2") (pinfunction "2_2") (pintype "passive"))
      (node (ref "U401") (pin "IN-") (pinfunction "IN-_IN-") (pintype "bidirectional"))
    )
    (net (code "15") (name "Net-(C411-Pad2)") (class "Default")
      (node (ref "C411") (pin "2") (pinfunction "2_2") (pintype "passive"))
      (node (ref "R418") (pin "1") (pinfunction "1_1") (pintype "passive"))
      (node (ref "R419") (pin "2") (pinfunction "2_2") (pintype "passive"))
      (node (ref "U401") (pin "OUT") (pinfunction "OUT_OUT") (pintype "bidirectional"))
    )
    (net (code "16") (name "Net-(U100-PB8-BOOT0)") (class "Default")
      (node (ref "BOOT") (pin "TP") (pinfunction "TP_TP") (pintype "input"))
      (node (ref "R101") (pin "2") (pinfunction "2_2") (pintype "passive"))
      (node (ref "U100") (pin "31") (pinfunction "PB8-BOOT0_31") (pintype "bidirectional"))
    )
    (net (code "17") (name "Net-(U100-PF0-OSC_IN)") (class "Default")
      (node (ref "C105") (pin "1") (pinfunction "1_1") (pintype "passive"))
      (node (ref "U100") (pin "2") (pinfunction "PF0-OSC_IN_2") (pintype "bidirectional"))
      (node (ref "X101") (pin "1") (pinfunction "1_1") (pintype "passive"))
    )
    (net (code "18") (name "Net-(U100-PF1-OSC_OUT)") (class "Default")
      (node (ref "C104") (pin "1") (pinfunction "1_1") (pintype "passive"))
      (node (ref "U100") (pin "3") (pinfunction "PF1-OSC_OUT_3") (pintype "bidirectional"))
      (node (ref "X101") (pin "3") (pinfunction "2_3") (pintype "passive"))
    )
    (net (code "19") (name "Net-(U200-EN)") (class "Default")
      (node (ref "EN") (pin "TP") (pinfunction "TP_TP") (pintype "input"))
      (node (ref "R202") (pin "1") (pinfunction "1_1") (pintype "passive"))
      (node (ref "R203") (pin "2") (pinfunction "2_2") (pintype "passive"))
      (node (ref "U200") (pin "1") (pinfunction "PS/SYNC_1") (pintype "input"))
      (node (ref "U200") (pin "14") (pinfunction "EN_14") (pintype "input"))
    )
    (net (code "20") (name "Net-(U200-FB)") (class "Default")
      (node (ref "R205") (pin "1") (pinfunction "1_1") (pintype "passive"))
      (node (ref "R206") (pin "2") (pinfunction "2_2") (pintype "passive"))
      (node (ref "U200") (pin "5") (pinfunction "FB_5") (pintype "passive"))
    )
    (net (code "21") (name "Net-(U200-FB2)") (class "Default")
      (node (ref "FB2") (pin "TP") (pinfunction "TP_TP") (pintype "input"))
      (node (ref "U200") (pin "6") (pinfunction "FB2_6") (pintype "passive"))
    )
    (net (code "22") (name "Net-(U200-L1)") (class "Default")
      (node (ref "L201") (pin "1") (pinfunction "1_1") (pintype "passive"))
      (node (ref "U200") (pin "11") (pinfunction "L1_11") (pintype "passive"))
    )
    (net (code "23") (name "Net-(U200-L2)") (class "Default")
      (node (ref "L201") (pin "2") (pinfunction "2_2") (pintype "passive"))
      (node (ref "U200") (pin "9") (pinfunction "L2_9") (pintype "passive"))
    )
    (net (code "24") (name "Net-(U200-PG)") (class "Default")
      (node (ref "PG") (pin "TP") (pinfunction "TP_TP") (pintype "input"))
      (node (ref "R207") (pin "1") (pinfunction "1_1") (pintype "passive"))
      (node (ref "U200") (pin "2") (pinfunction "PG_2") (pintype "open_collector"))
    )
    (net (code "25") (name "Net-(U200-VAUX)") (class "Default")
      (node (ref "C204") (pin "1") (pinfunction "1_1") (pintype "passive"))
      (node (ref "U200") (pin "3") (pinfunction "VAUX_3") (pintype "output"))
    )
    (net (code "26") (name "Net-(U200-VIN)") (class "Default")
      (node (ref "C201") (pin "1") (pinfunction "1_1") (pintype "passive"))
      (node (ref "C202") (pin "1") (pinfunction "1_1") (pintype "passive"))
      (node (ref "C203") (pin "1") (pinfunction "1_1") (pintype "passive"))
      (node (ref "R201") (pin "1") (pinfunction "1_1") (pintype "passive"))
      (node (ref "R202") (pin "2") (pinfunction "2_2") (pintype "passive"))
      (node (ref "U200") (pin "12-13") (pinfunction "VIN_12-13") (pintype "power_in"))
    )
    (net (code "27") (name "Net-(U200-VSEL)") (class "Default")
      (node (ref "R204") (pin "2") (pinfunction "2_2") (pintype "passive"))
      (node (ref "U200") (pin "15") (pinfunction "VSEL_15") (pintype "input"))
      (node (ref "VSEL") (pin "TP") (pinfunction "TP_TP") (pintype "input"))
    )
    (net (code "28") (name "Net-(U300-OUTU)") (class "Default")
      (node (ref "JP301") (pin "1") (pinfunction "1_1") (pintype "passive"))
      (node (ref "U300") (pin "3") (pinfunction "OUTU_3") (pintype "output"))
    )
    (net (code "29") (name "Net-(U300-OUTV)") (class "Default")
      (node (ref "JP301") (pin "2") (pinfunction "2_2") (pintype "passive"))
      (node (ref "U300") (pin "8") (pinfunction "OUTV_8") (pintype "output"))
    )
    (net (code "30") (name "Net-(U300-OUTW)") (class "Default")
      (node (ref "JP301") (pin "3") (pinfunction "3_3") (pintype "passive"))
      (node (ref "U300") (pin "10") (pinfunction "OUTW_10") (pintype "output"))
    )
    (net (code "31") (name "Net-(U300-SENSEU)") (class "Default")
      (node (ref "R309") (pin "1") (pinfunction "1_1") (pintype "passive"))
      (node (ref "R310") (pin "2") (pinfunction "2_2") (pintype "passive"))
      (node (ref "R311") (pin "2") (pinfunction "2_2") (pintype "passive"))
      (node (ref "U300") (pin "4") (pinfunction "SENSEU_4") (pintype "output"))
      (node (ref "U300") (pin "9") (pinfunction "SENSEVW_9") (pintype "output"))
    )
    (net (code "32") (name "Net-(U300-VS)") (class "Default")
      (node (ref "C301") (pin "1") (pinfunction "1_1") (pintype "passive"))
      (node (ref "C302") (pin "1") (pinfunction "1_1") (pintype "passive"))
      (node (ref "C303") (pin "1") (pinfunction "1_1") (pintype "passive"))
      (node (ref "R303") (pin "1") (pinfunction "1_1") (pintype "passive"))
      (node (ref "U300") (pin "6") (pinfunction "VS_6") (pintype "power_in"))
    )
    (net (code "33") (name "Net-(U302-A)") (class "Default")
      (node (ref "JP302") (pin "1") (pinfunction "1_1") (pintype "passive"))
      (node (ref "U302") (pin "7") (pinfunction "A_7") (pintype "output"))
    )
    (net (code "34") (name "Net-(U302-B)") (class "Default")
      (node (ref "JP302") (pin "2") (pinfunction "2_2") (pintype "passive"))
      (node (ref "U302") (pin "6") (pinfunction "B_6") (pintype "output"))
    )
    (net (code "35") (name "Net-(U302-MOSI)") (class "Default")
      (node (ref "R315") (pin "2") (pinfunction "2_2") (pintype "passive"))
      (node (ref "U302") (pin "4") (pinfunction "MOSI_4") (pintype "input"))
    )
    (net (code "36") (name "Net-(U400-OUTA1)") (class "Default")
      (node (ref "JP401") (pin "1") (pinfunction "1_1") (pintype "passive"))
      (node (ref "U400") (pin "10") (pinfunction "OUTB1_10") (pintype "output"))
      (node (ref "U400") (pin "3") (pinfunction "OUTA1_3") (pintype "output"))
    )
    (net (code "37") (name "Net-(U400-OUTA2)") (class "Default")
      (node (ref "JP401") (pin "2") (pinfunction "2_2") (pintype "passive"))
      (node (ref "U400") (pin "5") (pinfunction "OUTA2_5") (pintype "output"))
      (node (ref "U400") (pin "8") (pinfunction "OUTB2_8") (pintype "output"))
    )
    (net (code "38") (name "Net-(U400-PH)") (class "Default")
      (node (ref "R405") (pin "1") (pinfunction "1_1") (pintype "passive"))
      (node (ref "U400") (pin "1") (pinfunction "PH_1") (pintype "input"))
    )
    (net (code "39") (name "Net-(U400-PWM)") (class "Default")
      (node (ref "R406") (pin "1") (pinfunction "1_1") (pintype "passive"))
      (node (ref "U400") (pin "2") (pinfunction "PWM_2") (pintype "input"))
    )
    (net (code "40") (name "Net-(U400-REF)") (class "Default")
      (node (ref "C407") (pin "2") (pinfunction "2_2") (pintype "passive"))
      (node (ref "R409") (pin "2") (pinfunction "2_2") (pintype "passive"))
      (node (ref "R410") (pin "1") (pinfunction "1_1") (pintype "passive"))
      (node (ref "U400") (pin "11") (pinfunction "REF_11") (pintype "passive"))
    )
    (net (code "41") (name "Net-(U400-SENSEA)") (class "Default")
      (node (ref "R414") (pin "1") (pinfunction "1_1") (pintype "passive"))
      (node (ref "R415") (pin "1") (pinfunction "1_1") (pintype "passive"))
      (node (ref "R416") (pin "1") (pinfunction "1_1") (pintype "passive"))
      (node (ref "U400") (pin "4") (pinfunction "SENSEA_4") (pintype "output"))
      (node (ref "U400") (pin "9") (pinfunction "SENSEB_9") (pintype "output"))
    )
    (net (code "42") (name "Net-(U400-TOFF)") (class "Default")
      (node (ref "R407") (pin "1") (pinfunction "1_1") (pintype "passive"))
      (node (ref "R408") (pin "1") (pinfunction "1_1") (pintype "passive"))
      (node (ref "U400") (pin "12") (pinfunction "TOFF_12") (pintype "passive"))
    )
    (net (code "43") (name "Net-(U400-VS)") (class "Default")
      (node (ref "C401") (pin "1") (pinfunction "1_1") (pintype "passive"))
      (node (ref "C402") (pin "1") (pinfunction "1_1") (pintype "passive"))
      (node (ref "C403") (pin "1") (pinfunction "1_1") (pintype "passive"))
      (node (ref "R403") (pin "1") (pinfunction "1_1") (pintype "passive"))
      (node (ref "U400") (pin "6") (pinfunction "VS_6") (pintype "power_in"))
    )
    (net (code "44") (name "PA0{slash}CURR_FDB_MAG") (class "Default")
      (node (ref "R419") (pin "1") (pinfunction "1_1") (pintype "passive"))
      (node (ref "U100") (pin "6") (pinfunction "PA0_6") (pintype "bidirectional"))
    )
    (net (code "45") (name "PA1{slash}CURR_FDB_BLDC") (class "Default")
      (node (ref "R314") (pin "1") (pinfunction "1_1") (pintype "passive"))
      (node (ref "U100") (pin "7") (pinfunction "PA1_7") (pintype "bidirectional"))
    )
    (net (code "46") (name "PA2{slash}USART2_TX") (class "Default")
      (node (ref "JP103") (pin "P$2") (pinfunction "TXO_P$2") (pintype "passive"))
      (node (ref "U100") (pin "8") (pinfunction "PA2_8") (pintype "bidirectional"))
    )
    (net (code "47") (name "PA3{slash}USART2_RX") (class "Default")
      (node (ref "JP103") (pin "P$3") (pinfunction "RXI_P$3") (pintype "passive"))
      (node (ref "U100") (pin "9") (pinfunction "PA3_9") (pintype "bidirectional"))
    )
    (net (code "48") (name "PA4{slash}FAULT_BLDC") (class "Default")
      (node (ref "C305") (pin "2") (pinfunction "2_2") (pintype "passive"))
      (node (ref "R302") (pin "1") (pinfunction "1_1") (pintype "passive"))
      (node (ref "U100") (pin "10") (pinfunction "PA4_10") (pintype "bidirectional"))
      (node (ref "U300") (pin "13") (pinfunction "EN/FAULT_13") (pintype "bidirectional"))
    )
    (net (code "49") (name "PA5{slash}SPI1_SCK") (class "Default")
      (node (ref "U100") (pin "11") (pinfunction "PA5_11") (pintype "bidirectional"))
      (node (ref "U302") (pin "2") (pinfunction "SCLK_2") (pintype "input"))
    )
    (net (code "50") (name "PA6{slash}SPI1_NSS") (class "Default")
      (node (ref "U100") (pin "12") (pinfunction "PA6_12") (pintype "bidirectional"))
      (node (ref "U302") (pin "1") (pinfunction "CSN_1") (pintype "input"))
    )
    (net (code "51") (name "PA7{slash}INUL") (class "Default")
      (node (ref "U100") (pin "13") (pinfunction "PA7_13") (pintype "bidirectional"))
      (node (ref "U300") (pin "1") (pinfunction "INUL_1") (pintype "input"))
    )
    (net (code "52") (name "PA8{slash}INUH{slash}PWM_MAG") (class "Default")
      (node (ref "R406") (pin "2") (pinfunction "2_2") (pintype "passive"))
      (node (ref "U100") (pin "18") (pinfunction "PA8_18") (pintype "bidirectional"))
      (node (ref "U300") (pin "2") (pinfunction "INUH_2") (pintype "input"))
    )
    (net (code "53") (name "PA9{slash}INVH{slash}DIR_MAG") (class "Default")
      (node (ref "R405") (pin "2") (pinfunction "2_2") (pintype "passive"))
      (node (ref "U100") (pin "19") (pinfunction "PA9_19") (pintype "bidirectional"))
      (node (ref "U300") (pin "16") (pinfunction "INVH_16") (pintype "input"))
    )
    (net (code "54") (name "PA10{slash}INWH") (class "Default")
      (node (ref "U100") (pin "20") (pinfunction "PA10_20") (pintype "bidirectional"))
      (node (ref "U300") (pin "12") (pinfunction "INWH_12") (pintype "input"))
    )
    (net (code "55") (name "PA15{slash}CAN_SILENT") (class "Default")
      (node (ref "U100") (pin "25") (pinfunction "PA15_25") (pintype "bidirectional"))
      (node (ref "U101") (pin "8") (pinfunction "S_8") (pintype "input"))
    )
    (net (code "56") (name "PB0{slash}INVL") (class "Default")
      (node (ref "U100") (pin "14") (pinfunction "PB0_14") (pintype "bidirectional"))
      (node (ref "U300") (pin "15") (pinfunction "INVL_15") (pintype "input"))
    )
    (net (code "57") (name "PB1{slash}INWL") (class "Default")
      (node (ref "U100") (pin "15") (pinfunction "PB1_15") (pintype "bidirectional"))
      (node (ref "U300") (pin "11") (pinfunction "INWL_11") (pintype "input"))
    )
    (net (code "58") (name "PB3{slash}EN_MAG") (class "Default")
      (node (ref "R402") (pin "2") (pinfunction "2_2") (pintype "passive"))
      (node (ref "U100") (pin "26") (pinfunction "PB3_26") (pintype "bidirectional"))
    )
    (net (code "59") (name "PB4{slash}SPI1_MISO") (class "Default")
      (node (ref "U100") (pin "27") (pinfunction "PB4_27") (pintype "bidirectional"))
      (node (ref "U302") (pin "3") (pinfunction "MISO_3") (pintype "output"))
    )
    (net (code "60") (name "PB5") (class "Default")
      (node (ref "U100") (pin "28") (pinfunction "PB5_28") (pintype "bidirectional"))
    )
    (net (code "61") (name "PB6{slash}EN_BLDC") (class "Default")
      (node (ref "R302") (pin "2") (pinfunction "2_2") (pintype "passive"))
      (node (ref "U100") (pin "29") (pinfunction "PB6_29") (pintype "bidirectional"))
    )
    (net (code "62") (name "PB7{slash}FAULT_MAG") (class "Default")
      (node (ref "C405") (pin "2") (pinfunction "2_2") (pintype "passive"))
      (node (ref "R402") (pin "1") (pinfunction "1_1") (pintype "passive"))
      (node (ref "U100") (pin "30") (pinfunction "PB7_30") (pintype "bidirectional"))
      (node (ref "U400") (pin "13") (pinfunction "EN/FAULT_13") (pintype "bidirectional"))
    )
    (net (code "63") (name "STBY{slash}RESET_BLDC") (class "Default")
      (node (ref "C304") (pin "2") (pinfunction "2_2") (pintype "passive"))
      (node (ref "R301") (pin "1") (pinfunction "1_1") (pintype "passive"))
      (node (ref "U300") (pin "14") (pinfunction "STBY/RESET_14") (pintype "input"))
    )
    (net (code "64") (name "STBY{slash}RESET_MAG") (class "Default")
      (node (ref "C404") (pin "2") (pinfunction "2_2") (pintype "passive"))
      (node (ref "R401") (pin "1") (pinfunction "1_1") (pintype "passive"))
      (node (ref "U400") (pin "14") (pinfunction "STBY/RESET_14") (pintype "bidirectional"))
    )
    (net (code "65") (name "SWCLK") (class "Default")
      (node (ref "J1") (pin "SWDCLK") (pinfunction "SWDCLK/TCK_SWDCLK") (pintype "passive"))
      (node (ref "U100") (pin "24") (pinfunction "PA14-SWCLK_24") (pintype "bidirectional"))
    )
    (net (code "66") (name "SWDIO") (class "Default")
      (node (ref "J1") (pin "SWDIO") (pinfunction "SWDIO/TMS_SWDIO") (pintype "passive"))
      (node (ref "U100") (pin "23") (pinfunction "PA13-SWDIO_23") (pintype "bidirectional"))
    )
    (net (code "67") (name "V_BATT") (class "Default")
      (node (ref "JP1") (pin "1") (pinfunction "1_1") (pintype "passive"))
      (node (ref "JP103") (pin "P$4") (pinfunction "VCC_P$4") (pintype "passive"))
      (node (ref "R201") (pin "2") (pinfunction "2_2") (pintype "passive"))
      (node (ref "R303") (pin "2") (pinfunction "2_2") (pintype "passive"))
      (node (ref "R403") (pin "2") (pinfunction "2_2") (pintype "passive"))
    )
    (net (code "68") (name "unconnected-(J1-NC{slash}TDI-PadNC)") (class "Default")
      (node (ref "J1") (pin "NC") (pinfunction "NC/TDI_NC") (pintype "passive"))
    )
    (net (code "69") (name "unconnected-(J1-PadGNDDET)") (class "Default")
      (node (ref "J1") (pin "GNDDET") (pinfunction "GNDDET_GNDDET") (pintype "passive"))
    )
    (net (code "70") (name "unconnected-(J1-SWO{slash}TDO-PadSWO)") (class "Default")
      (node (ref "J1") (pin "SWO") (pinfunction "SWO/TDO_SWO") (pintype "passive"))
    )
    (net (code "71") (name "unconnected-(JP103-CTS-PadP$5)") (class "Default")
      (node (ref "JP103") (pin "P$5") (pinfunction "CTS_P$5") (pintype "passive"))
    )
    (net (code "72") (name "unconnected-(JP103-DTR-PadP$1)") (class "Default")
      (node (ref "JP103") (pin "P$1") (pinfunction "DTR_P$1") (pintype "passive"))
    )
    (net (code "73") (name "unconnected-(U302-I{slash}PWM-Pad14)") (class "Default")
      (node (ref "U302") (pin "14") (pinfunction "I/PWM_14") (pintype "output"))
    )
    (net (code "74") (name "unconnected-(U302-U-Pad10)") (class "Default")
      (node (ref "U302") (pin "10") (pinfunction "U_10") (pintype "output"))
    )
    (net (code "75") (name "unconnected-(U302-V-Pad9)") (class "Default")
      (node (ref "U302") (pin "9") (pinfunction "V_9") (pintype "output"))
    )
    (net (code "76") (name "unconnected-(U302-W{slash}PWM-Pad8)") (class "Default")
      (node (ref "U302") (pin "8") (pinfunction "W/PWM_8") (pintype "output"))
    )
  )
)
